# bluetooth_atmega32u4.net
KiCad netlist of a schematic drawn in EAGLE
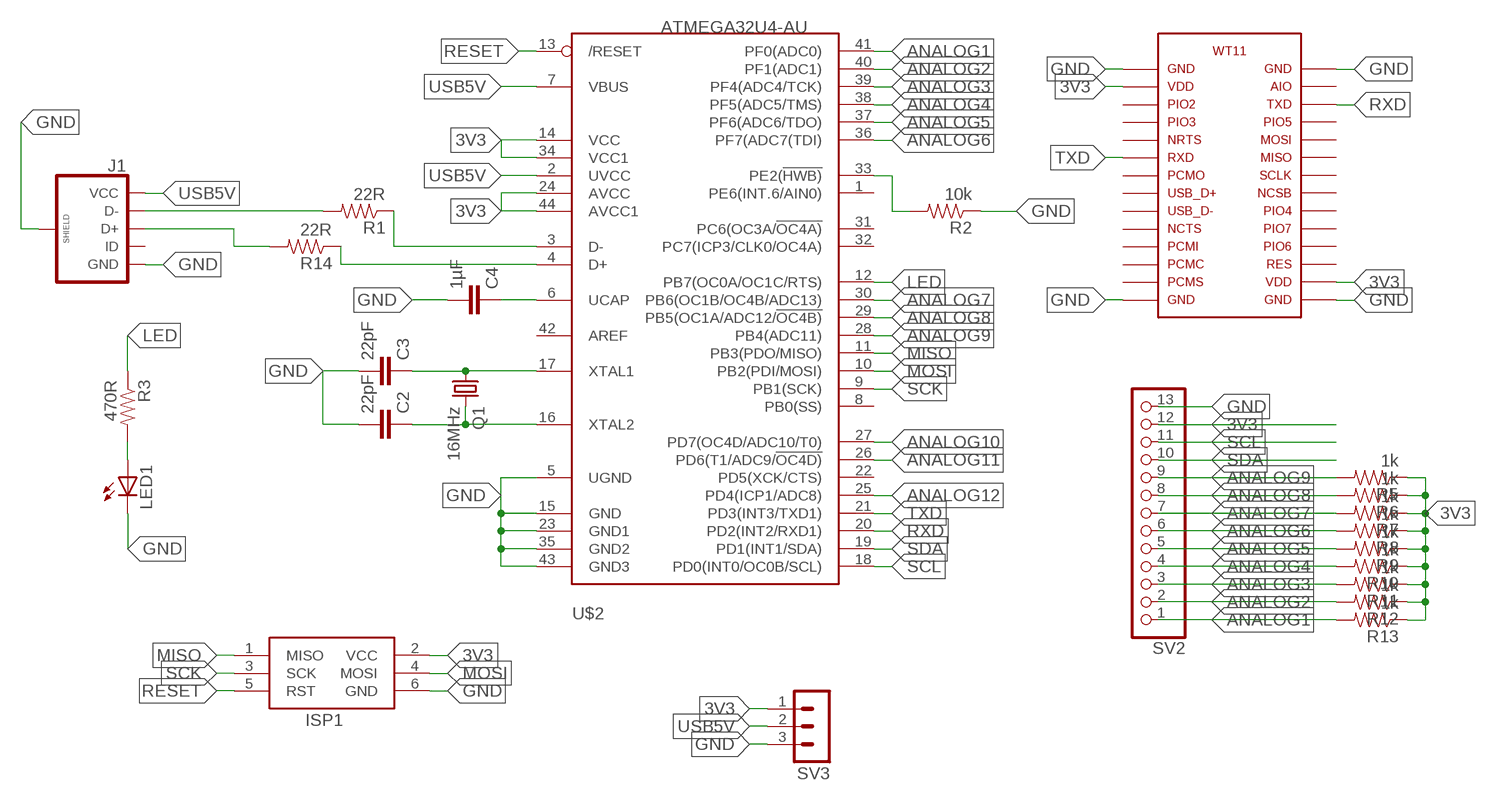
[diagram p0: schematic, sheet 1]

(export (version "E")
  (design (tool "Eeschema 10.0.6"))
  (components
    (comp (ref "C2")
      (value "22pF")
      (footprint "eagle-import:0805")
      (libsource (lib "eagle-import") (part "CAP0805"))
    )
    (comp (ref "C3")
      (value "22pF")
      (footprint "eagle-import:0805")
      (libsource (lib "eagle-import") (part "CAP0805"))
    )
    (comp (ref "C4")
      (value "1µF")
      (footprint "eagle-import:0805")
      (libsource (lib "eagle-import") (part "CAP0805"))
    )
    (comp (ref "ISP1")
      (value "AVRISP-6")
      (footprint "eagle-import:AVRISP")
      (libsource (lib "eagle-import") (part "AVRISP-6"))
    )
    (comp (ref "J1")
      (value "USB_MICROB_PLUGCONN-11752")
      (footprint "eagle-import:USB-B-MICRO-SMD_V03")
      (libsource (lib "eagle-import") (part "USB_MICROB_PLUGCONN-11752"))
    )
    (comp (ref "LED1")
      (value "LEDCHIPLED_0805")
      (footprint "eagle-import:CHIPLED_0805")
      (libsource (lib "eagle-import") (part "LEDCHIPLED_0805"))
    )
    (comp (ref "Q1")
      (value "16MHz")
      (footprint "eagle-import:CTS406")
      (libsource (lib "eagle-import") (part "CRYSTALCTS406"))
    )
    (comp (ref "R1")
      (value "22R")
      (footprint "eagle-import:0805")
      (libsource (lib "eagle-import") (part "RESISTOR0805-RES"))
    )
    (comp (ref "R2")
      (value "10k")
      (footprint "eagle-import:0805")
      (libsource (lib "eagle-import") (part "RESISTOR0805-RES"))
    )
    (comp (ref "R3")
      (value "470R")
      (footprint "eagle-import:0805")
      (libsource (lib "eagle-import") (part "RESISTOR0805-RES"))
    )
    (comp (ref "R5")
      (value "1k")
      (footprint "eagle-import:0805")
      (libsource (lib "eagle-import") (part "RESISTOR0805-RES"))
    )
    (comp (ref "R6")
      (value "1k")
      (footprint "eagle-import:0805")
      (libsource (lib "eagle-import") (part "RESISTOR0805-RES"))
    )
    (comp (ref "R7")
      (value "1k")
      (footprint "eagle-import:0805")
      (libsource (lib "eagle-import") (part "RESISTOR0805-RES"))
    )
    (comp (ref "R8")
      (value "1k")
      (footprint "eagle-import:0805")
      (libsource (lib "eagle-import") (part "RESISTOR0805-RES"))
    )
    (comp (ref "R9")
      (value "1k")
      (footprint "eagle-import:0805")
      (libsource (lib "eagle-import") (part "RESISTOR0805-RES"))
    )
    (comp (ref "R10")
      (value "1k")
      (footprint "eagle-import:0805")
      (libsource (lib "eagle-import") (part "RESISTOR0805-RES"))
    )
    (comp (ref "R11")
      (value "1k")
      (footprint "eagle-import:0805")
      (libsource (lib "eagle-import") (part "RESISTOR0805-RES"))
    )
    (comp (ref "R12")
      (value "1k")
      (footprint "eagle-import:0805")
      (libsource (lib "eagle-import") (part "RESISTOR0805-RES"))
    )
    (comp (ref "R13")
      (value "1k")
      (footprint "eagle-import:0805")
      (libsource (lib "eagle-import") (part "RESISTOR0805-RES"))
    )
    (comp (ref "R14")
      (value "22R")
      (footprint "eagle-import:0805")
      (libsource (lib "eagle-import") (part "RESISTOR0805-RES"))
    )
    (comp (ref "SV2")
      (value "PINHD-1X13_WEARABLE")
      (footprint "eagle-import:1X13-WEARABLE")
      (libsource (lib "eagle-import") (part "PINHD-1X13_WEARABLE"))
    )
    (comp (ref "SV3")
      (value "MA03-1")
      (footprint "eagle-import:MA03-1")
      (libsource (lib "eagle-import") (part "MA03-1"))
    )
    (comp (ref "U$2")
      (value "ATMEGA32U4-AU")
      (footprint "eagle-import:TQFP44")
      (libsource (lib "eagle-import") (part "ATMEGA32U4-AU"))
    )
    (comp (ref "WT11")
      (value "BLUEGIGAWT11-LONG-PADS")
      (footprint "eagle-import:BLUEGIGAWT11-LONGPADS")
      (libsource (lib "eagle-import") (part "BLUEGIGAWT11-LONG-PADS"))
    )
  )
  (nets
    (net (code "1") (name "3V3") (class "Default")
      (node (ref "ISP1") (pin "2") (pinfunction "VCC_2") (pintype "power_in"))
      (node (ref "R10") (pin "1") (pinfunction "1_1") (pintype "passive"))
      (node (ref "R11") (pin "1") (pinfunction "1_1") (pintype "passive"))
      (node (ref "R12") (pin "1") (pinfunction "1_1") (pintype "passive"))
      (node (ref "R13") (pin "1") (pinfunction "1_1") (pintype "passive"))
      (node (ref "R5") (pin "1") (pinfunction "1_1") (pintype "passive"))
      (node (ref "R6") (pin "1") (pinfunction "1_1") (pintype "passive"))
      (node (ref "R7") (pin "1") (pinfunction "1_1") (pintype "passive"))
      (node (ref "R8") (pin "1") (pinfunction "1_1") (pintype "passive"))
      (node (ref "R9") (pin "1") (pinfunction "1_1") (pintype "passive"))
      (node (ref "SV2") (pin "12") (pinfunction "12_12") (pintype "passive"))
      (node (ref "SV3") (pin "1") (pinfunction "1_1") (pintype "passive"))
      (node (ref "U$2") (pin "14") (pinfunction "VCC_14") (pintype "bidirectional"))
      (node (ref "U$2") (pin "24") (pinfunction "AVCC_24") (pintype "bidirectional"))
      (node (ref "U$2") (pin "34") (pinfunction "VCC1_34") (pintype "bidirectional"))
      (node (ref "U$2") (pin "44") (pinfunction "AVCC1_44") (pintype "bidirectional"))
      (node (ref "WT11") (pin "16") (pinfunction "16_16") (pintype "bidirectional"))
      (node (ref "WT11") (pin "2") (pinfunction "2_2") (pintype "bidirectional"))
    )
    (net (code "2") (name "ANALOG1") (class "Default")
      (node (ref "R13") (pin "2") (pinfunction "2_2") (pintype "passive"))
      (node (ref "SV2") (pin "1") (pinfunction "1_1") (pintype "passive"))
      (node (ref "U$2") (pin "41") (pinfunction "PF0(ADC0)_41") (pintype "bidirectional"))
    )
    (net (code "3") (name "ANALOG2") (class "Default")
      (node (ref "R12") (pin "2") (pinfunction "2_2") (pintype "passive"))
      (node (ref "SV2") (pin "2") (pinfunction "2_2") (pintype "passive"))
      (node (ref "U$2") (pin "40") (pinfunction "PF1(ADC1)_40") (pintype "bidirectional"))
    )
    (net (code "4") (name "ANALOG3") (class "Default")
      (node (ref "R11") (pin "2") (pinfunction "2_2") (pintype "passive"))
      (node (ref "SV2") (pin "3") (pinfunction "3_3") (pintype "passive"))
      (node (ref "U$2") (pin "39") (pinfunction "PF4(ADC4/TCK)_39") (pintype "bidirectional"))
    )
    (net (code "5") (name "ANALOG4") (class "Default")
      (node (ref "R10") (pin "2") (pinfunction "2_2") (pintype "passive"))
      (node (ref "SV2") (pin "4") (pinfunction "4_4") (pintype "passive"))
      (node (ref "U$2") (pin "38") (pinfunction "PF5(ADC5/TMS)_38") (pintype "bidirectional"))
    )
    (net (code "6") (name "ANALOG5") (class "Default")
      (node (ref "R9") (pin "2") (pinfunction "2_2") (pintype "passive"))
      (node (ref "SV2") (pin "5") (pinfunction "5_5") (pintype "passive"))
      (node (ref "U$2") (pin "37") (pinfunction "PF6(ADC6/TDO)_37") (pintype "bidirectional"))
    )
    (net (code "7") (name "ANALOG6") (class "Default")
      (node (ref "R8") (pin "2") (pinfunction "2_2") (pintype "passive"))
      (node (ref "SV2") (pin "6") (pinfunction "6_6") (pintype "passive"))
      (node (ref "U$2") (pin "36") (pinfunction "PF7(ADC7(TDI)_36") (pintype "bidirectional"))
    )
    (net (code "8") (name "ANALOG7") (class "Default")
      (node (ref "R7") (pin "2") (pinfunction "2_2") (pintype "passive"))
      (node (ref "SV2") (pin "7") (pinfunction "7_7") (pintype "passive"))
      (node (ref "U$2") (pin "30") (pinfunction "PB6(OC1B/OC4B/ADC13)_30") (pintype "bidirectional"))
    )
    (net (code "9") (name "ANALOG8") (class "Default")
      (node (ref "R6") (pin "2") (pinfunction "2_2") (pintype "passive"))
      (node (ref "SV2") (pin "8") (pinfunction "8_8") (pintype "passive"))
      (node (ref "U$2") (pin "29") (pinfunction "PB5(OC1A/ADC12/~{OC4B})_29") (pintype "bidirectional"))
    )
    (net (code "10") (name "ANALOG9") (class "Default")
      (node (ref "R5") (pin "2") (pinfunction "2_2") (pintype "passive"))
      (node (ref "SV2") (pin "9") (pinfunction "9_9") (pintype "passive"))
      (node (ref "U$2") (pin "28") (pinfunction "PB4(ADC11)_28") (pintype "bidirectional"))
    )
    (net (code "11") (name "ANALOG10") (class "Default")
      (node (ref "U$2") (pin "27") (pinfunction "PD7(OC4D/ADC10/T0)_27") (pintype "bidirectional"))
    )
    (net (code "12") (name "ANALOG11") (class "Default")
      (node (ref "U$2") (pin "26") (pinfunction "PD6(T1/ADC9/~{OC4D})_26") (pintype "bidirectional"))
    )
    (net (code "13") (name "ANALOG12") (class "Default")
      (node (ref "U$2") (pin "25") (pinfunction "PD4(ICP1/ADC8)_25") (pintype "bidirectional"))
    )
    (net (code "14") (name "GND") (class "Default")
      (node (ref "C2") (pin "2") (pinfunction "2_2") (pintype "passive"))
      (node (ref "C3") (pin "2") (pinfunction "2_2") (pintype "passive"))
      (node (ref "C4") (pin "2") (pinfunction "2_2") (pintype "passive"))
      (node (ref "ISP1") (pin "6") (pinfunction "GND_6") (pintype "power_in"))
      (node (ref "J1") (pin "GND") (pinfunction "GND_GND") (pintype "bidirectional"))
      (node (ref "J1") (pin "SHIELD1") (pinfunction "SHIELD_SHIELD1") (pintype "bidirectional"))
      (node (ref "J1") (pin "SHIELD2") (pinfunction "SHIELD_SHIELD2") (pintype "bidirectional"))
      (node (ref "J1") (pin "SHIELD3") (pinfunction "SHIELD_SHIELD3") (pintype "bidirectional"))
      (node (ref "LED1") (pin "C") (pinfunction "C_C") (pintype "passive"))
      (node (ref "R2") (pin "1") (pinfunction "1_1") (pintype "passive"))
      (node (ref "SV2") (pin "13") (pinfunction "13_13") (pintype "passive"))
      (node (ref "SV3") (pin "3") (pinfunction "3_3") (pintype "passive"))
      (node (ref "U$2") (pin "15") (pinfunction "GND_15") (pintype "bidirectional"))
      (node (ref "U$2") (pin "23") (pinfunction "GND1_23") (pintype "bidirectional"))
      (node (ref "U$2") (pin "35") (pinfunction "GND2_35") (pintype "bidirectional"))
      (node (ref "U$2") (pin "43") (pinfunction "GND3_43") (pintype "bidirectional"))
      (node (ref "U$2") (pin "5") (pinfunction "UGND_5") (pintype "bidirectional"))
      (node (ref "WT11") (pin "1") (pinfunction "1_1") (pintype "bidirectional"))
      (node (ref "WT11") (pin "14") (pinfunction "14_14") (pintype "bidirectional"))
      (node (ref "WT11") (pin "15") (pinfunction "15_15") (pintype "bidirectional"))
      (node (ref "WT11") (pin "28") (pinfunction "28_28") (pintype "bidirectional"))
    )
    (net (code "15") (name "LED") (class "Default")
      (node (ref "R3") (pin "1") (pinfunction "1_1") (pintype "passive"))
      (node (ref "U$2") (pin "12") (pinfunction "PB7(OC0A/OC1C/RTS)_12") (pintype "bidirectional"))
    )
    (net (code "16") (name "MISO") (class "Default")
      (node (ref "ISP1") (pin "1") (pinfunction "MISO_1") (pintype "input"))
      (node (ref "U$2") (pin "11") (pinfunction "PB3(PDO/MISO)_11") (pintype "bidirectional"))
    )
    (net (code "17") (name "MOSI") (class "Default")
      (node (ref "ISP1") (pin "4") (pinfunction "MOSI_4") (pintype "output"))
      (node (ref "U$2") (pin "10") (pinfunction "PB2(PDI/MOSI)_10") (pintype "bidirectional"))
    )
    (net (code "18") (name "Net-(J1-PadD+)") (class "Default")
      (node (ref "J1") (pin "D+") (pinfunction "D+_D+") (pintype "bidirectional"))
      (node (ref "R14") (pin "2") (pinfunction "2_2") (pintype "passive"))
    )
    (net (code "19") (name "Net-(J1-PadD-)") (class "Default")
      (node (ref "J1") (pin "D-") (pinfunction "D-_D-") (pintype "bidirectional"))
      (node (ref "R1") (pin "2") (pinfunction "2_2") (pintype "passive"))
    )
    (net (code "20") (name "Net-(LED1-PadA)") (class "Default")
      (node (ref "LED1") (pin "A") (pinfunction "A_A") (pintype "passive"))
      (node (ref "R3") (pin "2") (pinfunction "2_2") (pintype "passive"))
    )
    (net (code "21") (name "Net-(Q1-2)") (class "Default")
      (node (ref "C2") (pin "1") (pinfunction "1_1") (pintype "passive"))
      (node (ref "Q1") (pin "3") (pinfunction "2_3") (pintype "passive"))
      (node (ref "U$2") (pin "16") (pinfunction "XTAL2_16") (pintype "bidirectional"))
    )
    (net (code "22") (name "Net-(U$2-D+)") (class "Default")
      (node (ref "R14") (pin "1") (pinfunction "1_1") (pintype "passive"))
      (node (ref "U$2") (pin "4") (pinfunction "D+_4") (pintype "bidirectional"))
    )
    (net (code "23") (name "Net-(U$2-D-)") (class "Default")
      (node (ref "R1") (pin "1") (pinfunction "1_1") (pintype "passive"))
      (node (ref "U$2") (pin "3") (pinfunction "D-_3") (pintype "bidirectional"))
    )
    (net (code "24") (name "Net-(U$2-PE2(~{HWB}))") (class "Default")
      (node (ref "R2") (pin "2") (pinfunction "2_2") (pintype "passive"))
      (node (ref "U$2") (pin "33") (pinfunction "PE2(~{HWB})_33") (pintype "bidirectional"))
    )
    (net (code "25") (name "Net-(U$2-UCAP)") (class "Default")
      (node (ref "C4") (pin "1") (pinfunction "1_1") (pintype "passive"))
      (node (ref "U$2") (pin "6") (pinfunction "UCAP_6") (pintype "bidirectional"))
    )
    (net (code "26") (name "Net-(U$2-XTAL1)") (class "Default")
      (node (ref "C3") (pin "1") (pinfunction "1_1") (pintype "passive"))
      (node (ref "Q1") (pin "1") (pinfunction "1_1") (pintype "passive"))
      (node (ref "U$2") (pin "17") (pinfunction "XTAL1_17") (pintype "bidirectional"))
    )
    (net (code "27") (name "RESET") (class "Default")
      (node (ref "ISP1") (pin "5") (pinfunction "RST_5") (pintype "output"))
      (node (ref "U$2") (pin "13") (pinfunction "/RESET_13") (pintype "bidirectional"))
    )
    (net (code "28") (name "RXD") (class "Default")
      (node (ref "U$2") (pin "20") (pinfunction "PD2(INT2/RXD1)_20") (pintype "bidirectional"))
      (node (ref "WT11") (pin "26") (pinfunction "26_26") (pintype "bidirectional"))
    )
    (net (code "29") (name "SCK") (class "Default")
      (node (ref "ISP1") (pin "3") (pinfunction "SCK_3") (pintype "output"))
      (node (ref "U$2") (pin "9") (pinfunction "PB1(SCK)_9") (pintype "bidirectional"))
    )
    (net (code "30") (name "SCL") (class "Default")
      (node (ref "SV2") (pin "11") (pinfunction "11_11") (pintype "passive"))
      (node (ref "U$2") (pin "18") (pinfunction "PD0(INT0/OC0B/SCL)_18") (pintype "bidirectional"))
    )
    (net (code "31") (name "SDA") (class "Default")
      (node (ref "SV2") (pin "10") (pinfunction "10_10") (pintype "passive"))
      (node (ref "U$2") (pin "19") (pinfunction "PD1(INT1/SDA)_19") (pintype "bidirectional"))
    )
    (net (code "32") (name "TXD") (class "Default")
      (node (ref "U$2") (pin "21") (pinfunction "PD3(INT3/TXD1)_21") (pintype "bidirectional"))
      (node (ref "WT11") (pin "6") (pinfunction "6_6") (pintype "bidirectional"))
    )
    (net (code "33") (name "USB5V") (class "Default")
      (node (ref "J1") (pin "VBUS") (pinfunction "VCC_VBUS") (pintype "bidirectional"))
      (node (ref "SV3") (pin "2") (pinfunction "2_2") (pintype "passive"))
      (node (ref "U$2") (pin "2") (pinfunction "UVCC_2") (pintype "bidirectional"))
      (node (ref "U$2") (pin "7") (pinfunction "VBUS_7") (pintype "bidirectional"))
    )
    (net (code "34") (name "unconnected-(J1-PadID)") (class "Default")
      (node (ref "J1") (pin "ID") (pinfunction "ID_ID") (pintype "bidirectional"))
    )
    (net (code "35") (name "unconnected-(U$2-AREF-Pad42)") (class "Default")
      (node (ref "U$2") (pin "42") (pinfunction "AREF_42") (pintype "bidirectional"))
    )
    (net (code "36") (name "unconnected-(U$2-PB0(SS)-Pad8)") (class "Default")
      (node (ref "U$2") (pin "8") (pinfunction "PB0(SS)_8") (pintype "bidirectional"))
    )
    (net (code "37") (name "unconnected-(U$2-PC6(OC3A{slash}~{OC4A})-Pad31)") (class "Default")
      (node (ref "U$2") (pin "31") (pinfunction "PC6(OC3A/~{OC4A})_31") (pintype "bidirectional"))
    )
    (net (code "38") (name "unconnected-(U$2-PC7(ICP3{slash}CLK0{slash}OC4A)-Pad32)") (class "Default")
      (node (ref "U$2") (pin "32") (pinfunction "PC7(ICP3/CLK0/OC4A)_32") (pintype "bidirectional"))
    )
    (net (code "39") (name "unconnected-(U$2-PD5(XCK{slash}CTS)-Pad22)") (class "Default")
      (node (ref "U$2") (pin "22") (pinfunction "PD5(XCK/CTS)_22") (pintype "bidirectional"))
    )
    (net (code "40") (name "unconnected-(U$2-PE6(INT.6{slash}AIN0)-Pad1)") (class "Default")
      (node (ref "U$2") (pin "1") (pinfunction "PE6(INT.6/AIN0)_1") (pintype "bidirectional"))
    )
    (net (code "41") (name "unconnected-(WT11-Pad3)") (class "Default")
      (node (ref "WT11") (pin "3") (pinfunction "3_3") (pintype "bidirectional"))
    )
    (net (code "42") (name "unconnected-(WT11-Pad4)") (class "Default")
      (node (ref "WT11") (pin "4") (pinfunction "4_4") (pintype "bidirectional"))
    )
    (net (code "43") (name "unconnected-(WT11-Pad5)") (class "Default")
      (node (ref "WT11") (pin "5") (pinfunction "5_5") (pintype "bidirectional"))
    )
    (net (code "44") (name "unconnected-(WT11-Pad7)") (class "Default")
      (node (ref "WT11") (pin "7") (pinfunction "7_7") (pintype "bidirectional"))
    )
    (net (code "45") (name "unconnected-(WT11-Pad8)") (class "Default")
      (node (ref "WT11") (pin "8") (pinfunction "8_8") (pintype "bidirectional"))
    )
    (net (code "46") (name "unconnected-(WT11-Pad9)") (class "Default")
      (node (ref "WT11") (pin "9") (pinfunction "9_9") (pintype "bidirectional"))
    )
    (net (code "47") (name "unconnected-(WT11-Pad10)") (class "Default")
      (node (ref "WT11") (pin "10") (pinfunction "10_10") (pintype "bidirectional"))
    )
    (net (code "48") (name "unconnected-(WT11-Pad11)") (class "Default")
      (node (ref "WT11") (pin "11") (pinfunction "11_11") (pintype "bidirectional"))
    )
    (net (code "49") (name "unconnected-(WT11-Pad12)") (class "Default")
      (node (ref "WT11") (pin "12") (pinfunction "12_12") (pintype "bidirectional"))
    )
    (net (code "50") (name "unconnected-(WT11-Pad13)") (class "Default")
      (node (ref "WT11") (pin "13") (pinfunction "13_13") (pintype "bidirectional"))
    )
    (net (code "51") (name "unconnected-(WT11-Pad17)") (class "Default")
      (node (ref "WT11") (pin "17") (pinfunction "17_17") (pintype "bidirectional"))
    )
    (net (code "52") (name "unconnected-(WT11-Pad18)") (class "Default")
      (node (ref "WT11") (pin "18") (pinfunction "18_18") (pintype "bidirectional"))
    )
    (net (code "53") (name "unconnected-(WT11-Pad19)") (class "Default")
      (node (ref "WT11") (pin "19") (pinfunction "19_19") (pintype "bidirectional"))
    )
    (net (code "54") (name "unconnected-(WT11-Pad20)") (class "Default")
      (node (ref "WT11") (pin "20") (pinfunction "20_20") (pintype "bidirectional"))
    )
    (net (code "55") (name "unconnected-(WT11-Pad21)") (class "Default")
      (node (ref "WT11") (pin "21") (pinfunction "21_21") (pintype "bidirectional"))
    )
    (net (code "56") (name "unconnected-(WT11-Pad22)") (class "Default")
      (node (ref "WT11") (pin "22") (pinfunction "22_22") (pintype "bidirectional"))
    )
    (net (code "57") (name "unconnected-(WT11-Pad23)") (class "Default")
      (node (ref "WT11") (pin "23") (pinfunction "23_23") (pintype "bidirectional"))
    )
    (net (code "58") (name "unconnected-(WT11-Pad24)") (class "Default")
      (node (ref "WT11") (pin "24") (pinfunction "24_24") (pintype "bidirectional"))
    )
    (net (code "59") (name "unconnected-(WT11-Pad25)") (class "Default")
      (node (ref "WT11") (pin "25") (pinfunction "25_25") (pintype "bidirectional"))
    )
    (net (code "60") (name "unconnected-(WT11-Pad27)") (class "Default")
      (node (ref "WT11") (pin "27") (pinfunction "27_27") (pintype "bidirectional"))
    )
  )
)
